# v1.net
KiCad netlist of a schematic drawn in EAGLE
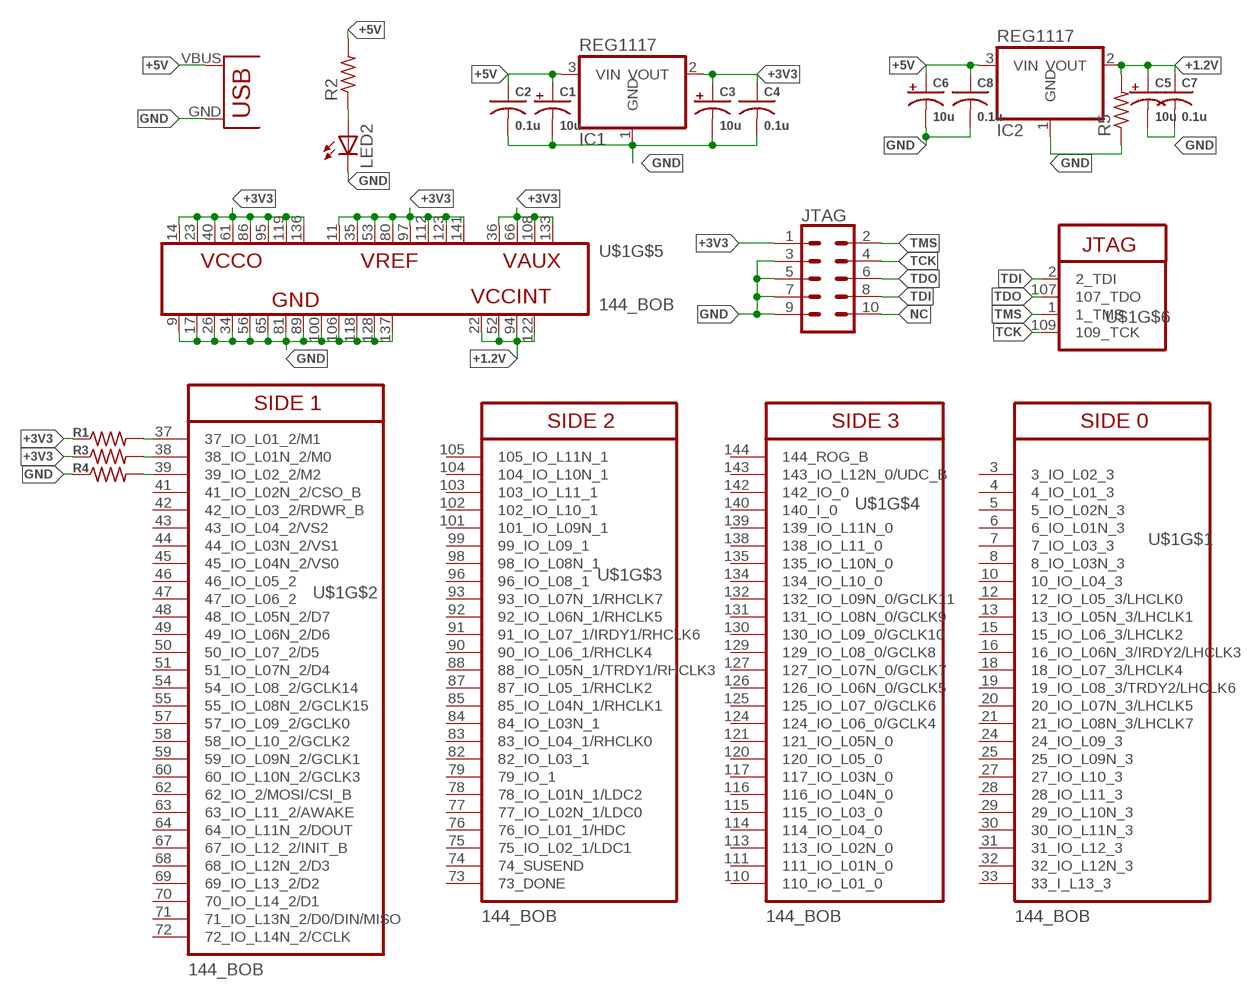
[diagram p0: schematic, sheet 1]

(export (version "E")
  (design (tool "Eeschema 10.0.6"))
  (components
    (comp (ref "C1")
      (value "10u")
      (footprint "eagle-import:B_3528-21R")
      (libsource (lib "eagle-import") (part "CAP_POL_16V"))
    )
    (comp (ref "C2")
      (value "0.1u")
      (footprint "eagle-import:C0603")
      (libsource (lib "eagle-import") (part "CAP0603"))
    )
    (comp (ref "C3")
      (value "10u")
      (footprint "eagle-import:B_3528-21R")
      (libsource (lib "eagle-import") (part "CAP_POL_16V"))
    )
    (comp (ref "C4")
      (value "0.1u")
      (footprint "eagle-import:C0603")
      (libsource (lib "eagle-import") (part "CAP0603"))
    )
    (comp (ref "C5")
      (value "10u")
      (footprint "eagle-import:B_3528-21R")
      (libsource (lib "eagle-import") (part "CAP_POL_16V"))
    )
    (comp (ref "C6")
      (value "10u")
      (footprint "eagle-import:B_3528-21R")
      (libsource (lib "eagle-import") (part "CAP_POL_16V"))
    )
    (comp (ref "C7")
      (value "0.1u")
      (footprint "eagle-import:C0603")
      (libsource (lib "eagle-import") (part "CAP0603"))
    )
    (comp (ref "C8")
      (value "0.1u")
      (footprint "eagle-import:C0603")
      (libsource (lib "eagle-import") (part "CAP0603"))
    )
    (comp (ref "IC1")
      (value "REG1117")
      (footprint "eagle-import:SOT223")
      (libsource (lib "eagle-import") (part "REG1117"))
    )
    (comp (ref "IC2")
      (value "REG1117")
      (footprint "eagle-import:SOT223")
      (libsource (lib "eagle-import") (part "REG1117"))
    )
    (comp (ref "JTAG")
      (value "CONN_05X2")
      (footprint "eagle-import:2X5-SHROUDED_LOCK_PROPER")
      (libsource (lib "eagle-import") (part "CONN_05X2"))
    )
    (comp (ref "LED2")
      (value "LED3MM")
      (footprint "eagle-import:LED3MM")
      (libsource (lib "eagle-import") (part "LED3MM"))
    )
    (comp (ref "R1")
      (value "RESISTOR0805")
      (footprint "eagle-import:R0805")
      (libsource (lib "eagle-import") (part "RESISTOR0805"))
    )
    (comp (ref "R2")
      (value "R-US_0204/7")
      (footprint "eagle-import:0204_7")
      (libsource (lib "eagle-import") (part "R-US_0204/7"))
    )
    (comp (ref "R3")
      (value "RESISTOR0805")
      (footprint "eagle-import:R0805")
      (libsource (lib "eagle-import") (part "RESISTOR0805"))
    )
    (comp (ref "R4")
      (value "RESISTOR0805")
      (footprint "eagle-import:R0805")
      (libsource (lib "eagle-import") (part "RESISTOR0805"))
    )
    (comp (ref "R5")
      (value "R-US_0204/7")
      (footprint "eagle-import:0204_7")
      (libsource (lib "eagle-import") (part "R-US_0204/7"))
    )
    (comp (ref "U$1")
      (value "144_BOB")
      (footprint "eagle-import:144_BOB")
      (libsource (lib "eagle-import") (part "144_BOB"))
    )
    (comp (ref "U$2")
      (value "USB(POWER)")
      (footprint "eagle-import:USB(POWER)")
      (libsource (lib "eagle-import") (part "USB(POWER)"))
    )
  )
  (nets
    (net (code "1") (name "+1.2V") (class "Default")
      (node (ref "C5") (pin "+") (pinfunction "+_+") (pintype "passive"))
      (node (ref "C7") (pin "1") (pinfunction "1_1") (pintype "passive"))
      (node (ref "IC2") (pin "2") (pinfunction "VOUT_2") (pintype "output"))
      (node (ref "R5") (pin "2") (pinfunction "2_2") (pintype "passive"))
      (node (ref "U$1") (pin "122") (pinfunction "122_VCCINT_122") (pintype "passive"))
      (node (ref "U$1") (pin "22") (pinfunction "22_VCCINT_22") (pintype "passive"))
      (node (ref "U$1") (pin "52") (pinfunction "52_VCCINT_52") (pintype "passive"))
      (node (ref "U$1") (pin "94") (pinfunction "94_VCCINT_94") (pintype "passive"))
    )
    (net (code "2") (name "+3V3") (class "Default")
      (node (ref "C3") (pin "+") (pinfunction "+_+") (pintype "passive"))
      (node (ref "C4") (pin "1") (pinfunction "1_1") (pintype "passive"))
      (node (ref "IC1") (pin "2") (pinfunction "VOUT_2") (pintype "output"))
      (node (ref "JTAG") (pin "1") (pinfunction "1_1") (pintype "passive"))
      (node (ref "R1") (pin "1") (pinfunction "1_1") (pintype "passive"))
      (node (ref "R3") (pin "1") (pinfunction "1_1") (pintype "passive"))
      (node (ref "U$1") (pin "108") (pinfunction "108_VAUX_108") (pintype "passive"))
      (node (ref "U$1") (pin "11") (pinfunction "11_VREF_11") (pintype "passive"))
      (node (ref "U$1") (pin "112") (pinfunction "112_VREF_112") (pintype "passive"))
      (node (ref "U$1") (pin "119") (pinfunction "119_VCCO_119") (pintype "passive"))
      (node (ref "U$1") (pin "123") (pinfunction "123_VREF_123") (pintype "passive"))
      (node (ref "U$1") (pin "133") (pinfunction "133_VAUX_133") (pintype "passive"))
      (node (ref "U$1") (pin "136") (pinfunction "136_VCCO_136") (pintype "passive"))
      (node (ref "U$1") (pin "14") (pinfunction "14_VCCO_14") (pintype "passive"))
      (node (ref "U$1") (pin "141") (pinfunction "141_VREF_141") (pintype "passive"))
      (node (ref "U$1") (pin "23") (pinfunction "23_VCCO_23") (pintype "passive"))
      (node (ref "U$1") (pin "35") (pinfunction "35_VREF_35") (pintype "passive"))
      (node (ref "U$1") (pin "36") (pinfunction "36_VAUX_36") (pintype "passive"))
      (node (ref "U$1") (pin "40") (pinfunction "40_VCCO_40") (pintype "passive"))
      (node (ref "U$1") (pin "53") (pinfunction "53_VREF_53") (pintype "passive"))
      (node (ref "U$1") (pin "61") (pinfunction "61_VCCO_61") (pintype "passive"))
      (node (ref "U$1") (pin "66") (pinfunction "66_VAUX_66") (pintype "passive"))
      (node (ref "U$1") (pin "80") (pinfunction "80_VREF_80") (pintype "passive"))
      (node (ref "U$1") (pin "86") (pinfunction "86_VCCO_86") (pintype "passive"))
      (node (ref "U$1") (pin "95") (pinfunction "95_VCCO_95") (pintype "passive"))
      (node (ref "U$1") (pin "97") (pinfunction "97_VREF_97") (pintype "passive"))
    )
    (net (code "3") (name "+5V") (class "Default")
      (node (ref "C1") (pin "+") (pinfunction "+_+") (pintype "passive"))
      (node (ref "C2") (pin "1") (pinfunction "1_1") (pintype "passive"))
      (node (ref "C6") (pin "+") (pinfunction "+_+") (pintype "passive"))
      (node (ref "C8") (pin "1") (pinfunction "1_1") (pintype "passive"))
      (node (ref "IC1") (pin "3") (pinfunction "VIN_3") (pintype "input"))
      (node (ref "IC2") (pin "3") (pinfunction "VIN_3") (pintype "input"))
      (node (ref "R2") (pin "2") (pinfunction "2_2") (pintype "passive"))
      (node (ref "U$2") (pin "VBUS") (pinfunction "VCC_VBUS") (pintype "power_in"))
    )
    (net (code "4") (name "GND") (class "Default")
      (node (ref "C1") (pin "-") (pinfunction "-_-") (pintype "passive"))
      (node (ref "C2") (pin "2") (pinfunction "2_2") (pintype "passive"))
      (node (ref "C3") (pin "-") (pinfunction "-_-") (pintype "passive"))
      (node (ref "C4") (pin "2") (pinfunction "2_2") (pintype "passive"))
      (node (ref "C5") (pin "-") (pinfunction "-_-") (pintype "passive"))
      (node (ref "C6") (pin "-") (pinfunction "-_-") (pintype "passive"))
      (node (ref "C7") (pin "2") (pinfunction "2_2") (pintype "passive"))
      (node (ref "C8") (pin "2") (pinfunction "2_2") (pintype "passive"))
      (node (ref "IC1") (pin "1") (pinfunction "GND_1") (pintype "power_in"))
      (node (ref "IC2") (pin "1") (pinfunction "GND_1") (pintype "power_in"))
      (node (ref "JTAG") (pin "3") (pinfunction "3_3") (pintype "passive"))
      (node (ref "JTAG") (pin "5") (pinfunction "5_5") (pintype "passive"))
      (node (ref "JTAG") (pin "7") (pinfunction "7_7") (pintype "passive"))
      (node (ref "JTAG") (pin "9") (pinfunction "9_9") (pintype "passive"))
      (node (ref "LED2") (pin "K") (pinfunction "C_K") (pintype "passive"))
      (node (ref "R4") (pin "1") (pinfunction "1_1") (pintype "passive"))
      (node (ref "R5") (pin "1") (pinfunction "1_1") (pintype "passive"))
      (node (ref "U$1") (pin "100") (pinfunction "100_GND_100") (pintype "passive"))
      (node (ref "U$1") (pin "106") (pinfunction "106_GND_106") (pintype "passive"))
      (node (ref "U$1") (pin "118") (pinfunction "118_GND_118") (pintype "passive"))
      (node (ref "U$1") (pin "128") (pinfunction "128_GND_128") (pintype "passive"))
      (node (ref "U$1") (pin "137") (pinfunction "137_GND_137") (pintype "passive"))
      (node (ref "U$1") (pin "17") (pinfunction "17_GND_17") (pintype "passive"))
      (node (ref "U$1") (pin "26") (pinfunction "26_GND_26") (pintype "passive"))
      (node (ref "U$1") (pin "34") (pinfunction "34_GND_34") (pintype "passive"))
      (node (ref "U$1") (pin "56") (pinfunction "56_GND_56") (pintype "passive"))
      (node (ref "U$1") (pin "65") (pinfunction "65_GND_65") (pintype "passive"))
      (node (ref "U$1") (pin "81") (pinfunction "81_GND_81") (pintype "passive"))
      (node (ref "U$1") (pin "89") (pinfunction "89_GND_89") (pintype "passive"))
      (node (ref "U$1") (pin "9") (pinfunction "9_GND_9") (pintype "passive"))
      (node (ref "U$2") (pin "GND") (pinfunction "GND_GND") (pintype "power_in"))
    )
    (net (code "5") (name "NC") (class "Default")
      (node (ref "JTAG") (pin "10") (pinfunction "10_10") (pintype "passive"))
    )
    (net (code "6") (name "Net-(LED2-PadA)") (class "Default")
      (node (ref "LED2") (pin "A") (pinfunction "A_A") (pintype "passive"))
      (node (ref "R2") (pin "1") (pinfunction "1_1") (pintype "passive"))
    )
    (net (code "7") (name "Net-(U$1B-37_IO_L01_2{slash}M1)") (class "Default")
      (node (ref "R1") (pin "2") (pinfunction "2_2") (pintype "passive"))
      (node (ref "U$1") (pin "37") (pinfunction "37_IO_L01_2/M1_37") (pintype "bidirectional"))
    )
    (net (code "8") (name "Net-(U$1B-38_IO_L01N_2{slash}M0)") (class "Default")
      (node (ref "R3") (pin "2") (pinfunction "2_2") (pintype "passive"))
      (node (ref "U$1") (pin "38") (pinfunction "38_IO_L01N_2/M0_38") (pintype "bidirectional"))
    )
    (net (code "9") (name "Net-(U$1B-39_IO_L02_2{slash}M2)") (class "Default")
      (node (ref "R4") (pin "2") (pinfunction "2_2") (pintype "passive"))
      (node (ref "U$1") (pin "39") (pinfunction "39_IO_L02_2/M2_39") (pintype "bidirectional"))
    )
    (net (code "10") (name "TCK") (class "Default")
      (node (ref "JTAG") (pin "4") (pinfunction "4_4") (pintype "passive"))
      (node (ref "U$1") (pin "109") (pinfunction "109_TCK_109") (pintype "passive"))
    )
    (net (code "11") (name "TDI") (class "Default")
      (node (ref "JTAG") (pin "8") (pinfunction "8_8") (pintype "passive"))
      (node (ref "U$1") (pin "2") (pinfunction "2_TDI_2") (pintype "passive"))
    )
    (net (code "12") (name "TDO") (class "Default")
      (node (ref "JTAG") (pin "6") (pinfunction "6_6") (pintype "passive"))
      (node (ref "U$1") (pin "107") (pinfunction "107_TDO_107") (pintype "passive"))
    )
    (net (code "13") (name "TMS") (class "Default")
      (node (ref "JTAG") (pin "2") (pinfunction "2_2") (pintype "passive"))
      (node (ref "U$1") (pin "1") (pinfunction "1_TMS_1") (pintype "passive"))
    )
    (net (code "14") (name "unconnected-(U$1A-3_IO_L02_3-Pad3)") (class "Default")
      (node (ref "U$1") (pin "3") (pinfunction "3_IO_L02_3_3") (pintype "bidirectional"))
    )
    (net (code "15") (name "unconnected-(U$1A-4_IO_L01_3-Pad4)") (class "Default")
      (node (ref "U$1") (pin "4") (pinfunction "4_IO_L01_3_4") (pintype "bidirectional"))
    )
    (net (code "16") (name "unconnected-(U$1A-5_IO_L02N_3-Pad5)") (class "Default")
      (node (ref "U$1") (pin "5") (pinfunction "5_IO_L02N_3_5") (pintype "bidirectional"))
    )
    (net (code "17") (name "unconnected-(U$1A-6_IO_L01N_3-Pad6)") (class "Default")
      (node (ref "U$1") (pin "6") (pinfunction "6_IO_L01N_3_6") (pintype "bidirectional"))
    )
    (net (code "18") (name "unconnected-(U$1A-7_IO_L03_3-Pad7)") (class "Default")
      (node (ref "U$1") (pin "7") (pinfunction "7_IO_L03_3_7") (pintype "bidirectional"))
    )
    (net (code "19") (name "unconnected-(U$1A-8_IO_L03N_3-Pad8)") (class "Default")
      (node (ref "U$1") (pin "8") (pinfunction "8_IO_L03N_3_8") (pintype "bidirectional"))
    )
    (net (code "20") (name "unconnected-(U$1A-10_IO_L04_3-Pad10)") (class "Default")
      (node (ref "U$1") (pin "10") (pinfunction "10_IO_L04_3_10") (pintype "bidirectional"))
    )
    (net (code "21") (name "unconnected-(U$1A-12_IO_L05_3{slash}LHCLK0-Pad12)") (class "Default")
      (node (ref "U$1") (pin "12") (pinfunction "12_IO_L05_3/LHCLK0_12") (pintype "bidirectional"))
    )
    (net (code "22") (name "unconnected-(U$1A-13_IO_L05N_3{slash}LHCLK1-Pad13)") (class "Default")
      (node (ref "U$1") (pin "13") (pinfunction "13_IO_L05N_3/LHCLK1_13") (pintype "bidirectional"))
    )
    (net (code "23") (name "unconnected-(U$1A-15_IO_L06_3{slash}LHCLK2-Pad15)") (class "Default")
      (node (ref "U$1") (pin "15") (pinfunction "15_IO_L06_3/LHCLK2_15") (pintype "bidirectional"))
    )
    (net (code "24") (name "unconnected-(U$1A-16_IO_L06N_3{slash}IRDY2{slash}LHCLK3-Pad16)") (class "Default")
      (node (ref "U$1") (pin "16") (pinfunction "16_IO_L06N_3/IRDY2/LHCLK3_16") (pintype "bidirectional"))
    )
    (net (code "25") (name "unconnected-(U$1A-18_IO_L07_3{slash}LHCLK4-Pad18)") (class "Default")
      (node (ref "U$1") (pin "18") (pinfunction "18_IO_L07_3/LHCLK4_18") (pintype "bidirectional"))
    )
    (net (code "26") (name "unconnected-(U$1A-19_IO_L08_3{slash}TRDY2{slash}LHCLK6-Pad19)") (class "Default")
      (node (ref "U$1") (pin "19") (pinfunction "19_IO_L08_3/TRDY2/LHCLK6_19") (pintype "bidirectional"))
    )
    (net (code "27") (name "unconnected-(U$1A-20_IO_L07N_3{slash}LHCLK5-Pad20)") (class "Default")
      (node (ref "U$1") (pin "20") (pinfunction "20_IO_L07N_3/LHCLK5_20") (pintype "bidirectional"))
    )
    (net (code "28") (name "unconnected-(U$1A-21_IO_L08N_3{slash}LHCLK7-Pad21)") (class "Default")
      (node (ref "U$1") (pin "21") (pinfunction "21_IO_L08N_3/LHCLK7_21") (pintype "bidirectional"))
    )
    (net (code "29") (name "unconnected-(U$1A-24_IO_L09_3-Pad24)") (class "Default")
      (node (ref "U$1") (pin "24") (pinfunction "24_IO_L09_3_24") (pintype "bidirectional"))
    )
    (net (code "30") (name "unconnected-(U$1A-25_IO_L09N_3-Pad25)") (class "Default")
      (node (ref "U$1") (pin "25") (pinfunction "25_IO_L09N_3_25") (pintype "bidirectional"))
    )
    (net (code "31") (name "unconnected-(U$1A-27_IO_L10_3-Pad27)") (class "Default")
      (node (ref "U$1") (pin "27") (pinfunction "27_IO_L10_3_27") (pintype "bidirectional"))
    )
    (net (code "32") (name "unconnected-(U$1A-28_IO_L11_3-Pad28)") (class "Default")
      (node (ref "U$1") (pin "28") (pinfunction "28_IO_L11_3_28") (pintype "bidirectional"))
    )
    (net (code "33") (name "unconnected-(U$1A-29_IO_L10N_3-Pad29)") (class "Default")
      (node (ref "U$1") (pin "29") (pinfunction "29_IO_L10N_3_29") (pintype "bidirectional"))
    )
    (net (code "34") (name "unconnected-(U$1A-30_IO_L11N_3-Pad30)") (class "Default")
      (node (ref "U$1") (pin "30") (pinfunction "30_IO_L11N_3_30") (pintype "bidirectional"))
    )
    (net (code "35") (name "unconnected-(U$1A-31_IO_L12_3-Pad31)") (class "Default")
      (node (ref "U$1") (pin "31") (pinfunction "31_IO_L12_3_31") (pintype "bidirectional"))
    )
    (net (code "36") (name "unconnected-(U$1A-32_IO_L12N_3-Pad32)") (class "Default")
      (node (ref "U$1") (pin "32") (pinfunction "32_IO_L12N_3_32") (pintype "bidirectional"))
    )
    (net (code "37") (name "unconnected-(U$1A-33_I_L13_3-Pad33)") (class "Default")
      (node (ref "U$1") (pin "33") (pinfunction "33_I_L13_3_33") (pintype "bidirectional"))
    )
    (net (code "38") (name "unconnected-(U$1B-41_IO_L02N_2{slash}CSO_B-Pad41)") (class "Default")
      (node (ref "U$1") (pin "41") (pinfunction "41_IO_L02N_2/CSO_B_41") (pintype "bidirectional"))
    )
    (net (code "39") (name "unconnected-(U$1B-42_IO_L03_2{slash}RDWR_B-Pad42)") (class "Default")
      (node (ref "U$1") (pin "42") (pinfunction "42_IO_L03_2/RDWR_B_42") (pintype "bidirectional"))
    )
    (net (code "40") (name "unconnected-(U$1B-43_IO_L04_2{slash}VS2-Pad43)") (class "Default")
      (node (ref "U$1") (pin "43") (pinfunction "43_IO_L04_2/VS2_43") (pintype "bidirectional"))
    )
    (net (code "41") (name "unconnected-(U$1B-44_IO_L03N_2{slash}VS1-Pad44)") (class "Default")
      (node (ref "U$1") (pin "44") (pinfunction "44_IO_L03N_2/VS1_44") (pintype "bidirectional"))
    )
    (net (code "42") (name "unconnected-(U$1B-45_IO_L04N_2{slash}VS0-Pad45)") (class "Default")
      (node (ref "U$1") (pin "45") (pinfunction "45_IO_L04N_2/VS0_45") (pintype "bidirectional"))
    )
    (net (code "43") (name "unconnected-(U$1B-46_IO_L05_2-Pad46)") (class "Default")
      (node (ref "U$1") (pin "46") (pinfunction "46_IO_L05_2_46") (pintype "bidirectional"))
    )
    (net (code "44") (name "unconnected-(U$1B-47_IO_L06_2-Pad47)") (class "Default")
      (node (ref "U$1") (pin "47") (pinfunction "47_IO_L06_2_47") (pintype "bidirectional"))
    )
    (net (code "45") (name "unconnected-(U$1B-48_IO_L05N_2{slash}D7-Pad48)") (class "Default")
      (node (ref "U$1") (pin "48") (pinfunction "48_IO_L05N_2/D7_48") (pintype "bidirectional"))
    )
    (net (code "46") (name "unconnected-(U$1B-49_IO_L06N_2{slash}D6-Pad49)") (class "Default")
      (node (ref "U$1") (pin "49") (pinfunction "49_IO_L06N_2/D6_49") (pintype "bidirectional"))
    )
    (net (code "47") (name "unconnected-(U$1B-50_IO_L07_2{slash}D5-Pad50)") (class "Default")
      (node (ref "U$1") (pin "50") (pinfunction "50_IO_L07_2/D5_50") (pintype "bidirectional"))
    )
    (net (code "48") (name "unconnected-(U$1B-51_IO_L07N_2{slash}D4-Pad51)") (class "Default")
      (node (ref "U$1") (pin "51") (pinfunction "51_IO_L07N_2/D4_51") (pintype "bidirectional"))
    )
    (net (code "49") (name "unconnected-(U$1B-54_IO_L08_2{slash}GCLK14-Pad54)") (class "Default")
      (node (ref "U$1") (pin "54") (pinfunction "54_IO_L08_2/GCLK14_54") (pintype "bidirectional"))
    )
    (net (code "50") (name "unconnected-(U$1B-55_IO_L08N_2{slash}GCLK15-Pad55)") (class "Default")
      (node (ref "U$1") (pin "55") (pinfunction "55_IO_L08N_2/GCLK15_55") (pintype "bidirectional"))
    )
    (net (code "51") (name "unconnected-(U$1B-57_IO_L09_2{slash}GCLK0-Pad57)") (class "Default")
      (node (ref "U$1") (pin "57") (pinfunction "57_IO_L09_2/GCLK0_57") (pintype "bidirectional"))
    )
    (net (code "52") (name "unconnected-(U$1B-58_IO_L10_2{slash}GCLK2-Pad58)") (class "Default")
      (node (ref "U$1") (pin "58") (pinfunction "58_IO_L10_2/GCLK2_58") (pintype "bidirectional"))
    )
    (net (code "53") (name "unconnected-(U$1B-59_IO_L09N_2{slash}GCLK1-Pad59)") (class "Default")
      (node (ref "U$1") (pin "59") (pinfunction "59_IO_L09N_2/GCLK1_59") (pintype "bidirectional"))
    )
    (net (code "54") (name "unconnected-(U$1B-60_IO_L10N_2{slash}GCLK3-Pad60)") (class "Default")
      (node (ref "U$1") (pin "60") (pinfunction "60_IO_L10N_2/GCLK3_60") (pintype "bidirectional"))
    )
    (net (code "55") (name "unconnected-(U$1B-62_IO_2{slash}MOSI{slash}CSI_B-Pad62)") (class "Default")
      (node (ref "U$1") (pin "62") (pinfunction "62_IO_2/MOSI/CSI_B_62") (pintype "bidirectional"))
    )
    (net (code "56") (name "unconnected-(U$1B-63_IO_L11_2{slash}AWAKE-Pad63)") (class "Default")
      (node (ref "U$1") (pin "63") (pinfunction "63_IO_L11_2/AWAKE_63") (pintype "bidirectional"))
    )
    (net (code "57") (name "unconnected-(U$1B-64_IO_L11N_2{slash}DOUT-Pad64)") (class "Default")
      (node (ref "U$1") (pin "64") (pinfunction "64_IO_L11N_2/DOUT_64") (pintype "bidirectional"))
    )
    (net (code "58") (name "unconnected-(U$1B-67_IO_L12_2{slash}INIT_B-Pad67)") (class "Default")
      (node (ref "U$1") (pin "67") (pinfunction "67_IO_L12_2/INIT_B_67") (pintype "bidirectional"))
    )
    (net (code "59") (name "unconnected-(U$1B-68_IO_L12N_2{slash}D3-Pad68)") (class "Default")
      (node (ref "U$1") (pin "68") (pinfunction "68_IO_L12N_2/D3_68") (pintype "bidirectional"))
    )
    (net (code "60") (name "unconnected-(U$1B-69_IO_L13_2{slash}D2-Pad69)") (class "Default")
      (node (ref "U$1") (pin "69") (pinfunction "69_IO_L13_2/D2_69") (pintype "bidirectional"))
    )
    (net (code "61") (name "unconnected-(U$1B-70_IO_L14_2{slash}D1-Pad70)") (class "Default")
      (node (ref "U$1") (pin "70") (pinfunction "70_IO_L14_2/D1_70") (pintype "bidirectional"))
    )
    (net (code "62") (name "unconnected-(U$1B-71_IO_L13N_2{slash}D0{slash}DIN{slash}MISO-Pad71)") (class "Default")
      (node (ref "U$1") (pin "71") (pinfunction "71_IO_L13N_2/D0/DIN/MISO_71") (pintype "bidirectional"))
    )
    (net (code "63") (name "unconnected-(U$1B-72_IO_L14N_2{slash}CCLK-Pad72)") (class "Default")
      (node (ref "U$1") (pin "72") (pinfunction "72_IO_L14N_2/CCLK_72") (pintype "bidirectional"))
    )
    (net (code "64") (name "unconnected-(U$1C-73_DONE-Pad73)") (class "Default")
      (node (ref "U$1") (pin "73") (pinfunction "73_DONE_73") (pintype "bidirectional"))
    )
    (net (code "65") (name "unconnected-(U$1C-74_SUSEND-Pad74)") (class "Default")
      (node (ref "U$1") (pin "74") (pinfunction "74_SUSEND_74") (pintype "bidirectional"))
    )
    (net (code "66") (name "unconnected-(U$1C-75_IO_L02_1{slash}LDC1-Pad75)") (class "Default")
      (node (ref "U$1") (pin "75") (pinfunction "75_IO_L02_1/LDC1_75") (pintype "bidirectional"))
    )
    (net (code "67") (name "unconnected-(U$1C-76_IO_L01_1{slash}HDC-Pad76)") (class "Default")
      (node (ref "U$1") (pin "76") (pinfunction "76_IO_L01_1/HDC_76") (pintype "bidirectional"))
    )
    (net (code "68") (name "unconnected-(U$1C-77_IO_L02N_1{slash}LDC0-Pad77)") (class "Default")
      (node (ref "U$1") (pin "77") (pinfunction "77_IO_L02N_1/LDC0_77") (pintype "bidirectional"))
    )
    (net (code "69") (name "unconnected-(U$1C-78_IO_L01N_1{slash}LDC2-Pad78)") (class "Default")
      (node (ref "U$1") (pin "78") (pinfunction "78_IO_L01N_1/LDC2_78") (pintype "bidirectional"))
    )
    (net (code "70") (name "unconnected-(U$1C-79_IO_1-Pad79)") (class "Default")
      (node (ref "U$1") (pin "79") (pinfunction "79_IO_1_79") (pintype "bidirectional"))
    )
    (net (code "71") (name "unconnected-(U$1C-82_IO_L03_1-Pad82)") (class "Default")
      (node (ref "U$1") (pin "82") (pinfunction "82_IO_L03_1_82") (pintype "bidirectional"))
    )
    (net (code "72") (name "unconnected-(U$1C-83_IO_L04_1{slash}RHCLK0-Pad83)") (class "Default")
      (node (ref "U$1") (pin "83") (pinfunction "83_IO_L04_1/RHCLK0_83") (pintype "bidirectional"))
    )
    (net (code "73") (name "unconnected-(U$1C-84_IO_L03N_1-Pad84)") (class "Default")
      (node (ref "U$1") (pin "84") (pinfunction "84_IO_L03N_1_84") (pintype "bidirectional"))
    )
    (net (code "74") (name "unconnected-(U$1C-85_IO_L04N_1{slash}RHCLK1-Pad85)") (class "Default")
      (node (ref "U$1") (pin "85") (pinfunction "85_IO_L04N_1/RHCLK1_85") (pintype "bidirectional"))
    )
    (net (code "75") (name "unconnected-(U$1C-87_IO_L05_1{slash}RHCLK2-Pad87)") (class "Default")
      (node (ref "U$1") (pin "87") (pinfunction "87_IO_L05_1/RHCLK2_87") (pintype "bidirectional"))
    )
    (net (code "76") (name "unconnected-(U$1C-88_IO_L05N_1{slash}TRDY1{slash}RHCLK3-Pad88)") (class "Default")
      (node (ref "U$1") (pin "88") (pinfunction "88_IO_L05N_1/TRDY1/RHCLK3_88") (pintype "bidirectional"))
    )
    (net (code "77") (name "unconnected-(U$1C-90_IO_L06_1{slash}RHCLK4-Pad90)") (class "Default")
      (node (ref "U$1") (pin "90") (pinfunction "90_IO_L06_1/RHCLK4_90") (pintype "bidirectional"))
    )
    (net (code "78") (name "unconnected-(U$1C-91_IO_L07_1{slash}IRDY1{slash}RHCLK6-Pad91)") (class "Default")
      (node (ref "U$1") (pin "91") (pinfunction "91_IO_L07_1/IRDY1/RHCLK6_91") (pintype "bidirectional"))
    )
    (net (code "79") (name "unconnected-(U$1C-92_IO_L06N_1{slash}RHCLK5-Pad92)") (class "Default")
      (node (ref "U$1") (pin "92") (pinfunction "92_IO_L06N_1/RHCLK5_92") (pintype "bidirectional"))
    )
    (net (code "80") (name "unconnected-(U$1C-93_IO_L07N_1{slash}RHCLK7-Pad93)") (class "Default")
      (node (ref "U$1") (pin "93") (pinfunction "93_IO_L07N_1/RHCLK7_93") (pintype "bidirectional"))
    )
    (net (code "81") (name "unconnected-(U$1C-96_IO_L08_1-Pad96)") (class "Default")
      (node (ref "U$1") (pin "96") (pinfunction "96_IO_L08_1_96") (pintype "bidirectional"))
    )
    (net (code "82") (name "unconnected-(U$1C-98_IO_L08N_1-Pad98)") (class "Default")
      (node (ref "U$1") (pin "98") (pinfunction "98_IO_L08N_1_98") (pintype "bidirectional"))
    )
    (net (code "83") (name "unconnected-(U$1C-99_IO_L09_1-Pad99)") (class "Default")
      (node (ref "U$1") (pin "99") (pinfunction "99_IO_L09_1_99") (pintype "bidirectional"))
    )
    (net (code "84") (name "unconnected-(U$1C-101_IO_L09N_1-Pad101)") (class "Default")
      (node (ref "U$1") (pin "101") (pinfunction "101_IO_L09N_1_101") (pintype "bidirectional"))
    )
    (net (code "85") (name "unconnected-(U$1C-102_IO_L10_1-Pad102)") (class "Default")
      (node (ref "U$1") (pin "102") (pinfunction "102_IO_L10_1_102") (pintype "bidirectional"))
    )
    (net (code "86") (name "unconnected-(U$1C-103_IO_L11_1-Pad103)") (class "Default")
      (node (ref "U$1") (pin "103") (pinfunction "103_IO_L11_1_103") (pintype "bidirectional"))
    )
    (net (code "87") (name "unconnected-(U$1C-104_IO_L10N_1-Pad104)") (class "Default")
      (node (ref "U$1") (pin "104") (pinfunction "104_IO_L10N_1_104") (pintype "bidirectional"))
    )
    (net (code "88") (name "unconnected-(U$1C-105_IO_L11N_1-Pad105)") (class "Default")
      (node (ref "U$1") (pin "105") (pinfunction "105_IO_L11N_1_105") (pintype "bidirectional"))
    )
    (net (code "89") (name "unconnected-(U$1D-110_IO_L01_0-Pad110)") (class "Default")
      (node (ref "U$1") (pin "110") (pinfunction "110_IO_L01_0_110") (pintype "bidirectional"))
    )
    (net (code "90") (name "unconnected-(U$1D-111_IO_L01N_0-Pad111)") (class "Default")
      (node (ref "U$1") (pin "111") (pinfunction "111_IO_L01N_0_111") (pintype "bidirectional"))
    )
    (net (code "91") (name "unconnected-(U$1D-113_IO_L02N_0-Pad113)") (class "Default")
      (node (ref "U$1") (pin "113") (pinfunction "113_IO_L02N_0_113") (pintype "bidirectional"))
    )
    (net (code "92") (name "unconnected-(U$1D-114_IO_L04_0-Pad114)") (class "Default")
      (node (ref "U$1") (pin "114") (pinfunction "114_IO_L04_0_114") (pintype "bidirectional"))
    )
    (net (code "93") (name "unconnected-(U$1D-115_IO_L03_0-Pad115)") (class "Default")
      (node (ref "U$1") (pin "115") (pinfunction "115_IO_L03_0_115") (pintype "bidirectional"))
    )
    (net (code "94") (name "unconnected-(U$1D-116_IO_L04N_0-Pad116)") (class "Default")
      (node (ref "U$1") (pin "116") (pinfunction "116_IO_L04N_0_116") (pintype "bidirectional"))
    )
    (net (code "95") (name "unconnected-(U$1D-117_IO_L03N_0-Pad117)") (class "Default")
      (node (ref "U$1") (pin "117") (pinfunction "117_IO_L03N_0_117") (pintype "bidirectional"))
    )
    (net (code "96") (name "unconnected-(U$1D-120_IO_L05_0-Pad120)") (class "Default")
      (node (ref "U$1") (pin "120") (pinfunction "120_IO_L05_0_120") (pintype "bidirectional"))
    )
    (net (code "97") (name "unconnected-(U$1D-121_IO_L05N_0-Pad121)") (class "Default")
      (node (ref "U$1") (pin "121") (pinfunction "121_IO_L05N_0_121") (pintype "bidirectional"))
    )
    (net (code "98") (name "unconnected-(U$1D-124_IO_L06_0{slash}GCLK4-Pad124)") (class "Default")
      (node (ref "U$1") (pin "124") (pinfunction "124_IO_L06_0/GCLK4_124") (pintype "bidirectional"))
    )
    (net (code "99") (name "unconnected-(U$1D-125_IO_L07_0{slash}GCLK6-Pad125)") (class "Default")
      (node (ref "U$1") (pin "125") (pinfunction "125_IO_L07_0/GCLK6_125") (pintype "bidirectional"))
    )
    (net (code "100") (name "unconnected-(U$1D-126_IO_L06N_0{slash}GCLK5-Pad126)") (class "Default")
      (node (ref "U$1") (pin "126") (pinfunction "126_IO_L06N_0/GCLK5_126") (pintype "bidirectional"))
    )
    (net (code "101") (name "unconnected-(U$1D-127_IO_L07N_0{slash}GCLK7-Pad127)") (class "Default")
      (node (ref "U$1") (pin "127") (pinfunction "127_IO_L07N_0/GCLK7_127") (pintype "bidirectional"))
    )
    (net (code "102") (name "unconnected-(U$1D-129_IO_L08_0{slash}GCLK8-Pad129)") (class "Default")
      (node (ref "U$1") (pin "129") (pinfunction "129_IO_L08_0/GCLK8_129") (pintype "bidirectional"))
    )
    (net (code "103") (name "unconnected-(U$1D-130_IO_L09_0{slash}GCLK10-Pad130)") (class "Default")
      (node (ref "U$1") (pin "130") (pinfunction "130_IO_L09_0/GCLK10_130") (pintype "bidirectional"))
    )
    (net (code "104") (name "unconnected-(U$1D-131_IO_L08N_0{slash}GCLK9-Pad131)") (class "Default")
      (node (ref "U$1") (pin "131") (pinfunction "131_IO_L08N_0/GCLK9_131") (pintype "bidirectional"))
    )
    (net (code "105") (name "unconnected-(U$1D-132_IO_L09N_0{slash}GCLK11-Pad132)") (class "Default")
      (node (ref "U$1") (pin "132") (pinfunction "132_IO_L09N_0/GCLK11_132") (pintype "bidirectional"))
    )
    (net (code "106") (name "unconnected-(U$1D-134_IO_L10_0-Pad134)") (class "Default")
      (node (ref "U$1") (pin "134") (pinfunction "134_IO_L10_0_134") (pintype "bidirectional"))
    )
    (net (code "107") (name "unconnected-(U$1D-135_IO_L10N_0-Pad135)") (class "Default")
      (node (ref "U$1") (pin "135") (pinfunction "135_IO_L10N_0_135") (pintype "bidirectional"))
    )
    (net (code "108") (name "unconnected-(U$1D-138_IO_L11_0-Pad138)") (class "Default")
      (node (ref "U$1") (pin "138") (pinfunction "138_IO_L11_0_138") (pintype "bidirectional"))
    )
    (net (code "109") (name "unconnected-(U$1D-139_IO_L11N_0-Pad139)") (class "Default")
      (node (ref "U$1") (pin "139") (pinfunction "139_IO_L11N_0_139") (pintype "bidirectional"))
    )
    (net (code "110") (name "unconnected-(U$1D-140_I_0-Pad140)") (class "Default")
      (node (ref "U$1") (pin "140") (pinfunction "140_I_0_140") (pintype "bidirectional"))
    )
    (net (code "111") (name "unconnected-(U$1D-142_IO_0-Pad142)") (class "Default")
      (node (ref "U$1") (pin "142") (pinfunction "142_IO_0_142") (pintype "bidirectional"))
    )
    (net (code "112") (name "unconnected-(U$1D-143_IO_L12N_0{slash}UDC_B-Pad143)") (class "Default")
      (node (ref "U$1") (pin "143") (pinfunction "143_IO_L12N_0/UDC_B_143") (pintype "bidirectional"))
    )
    (net (code "113") (name "unconnected-(U$1D-144_ROG_B-Pad144)") (class "Default")
      (node (ref "U$1") (pin "144") (pinfunction "144_ROG_B_144") (pintype "bidirectional"))
    )
  )
)
